# buffer.net
KiCad netlist of a schematic drawn in Altium Designer
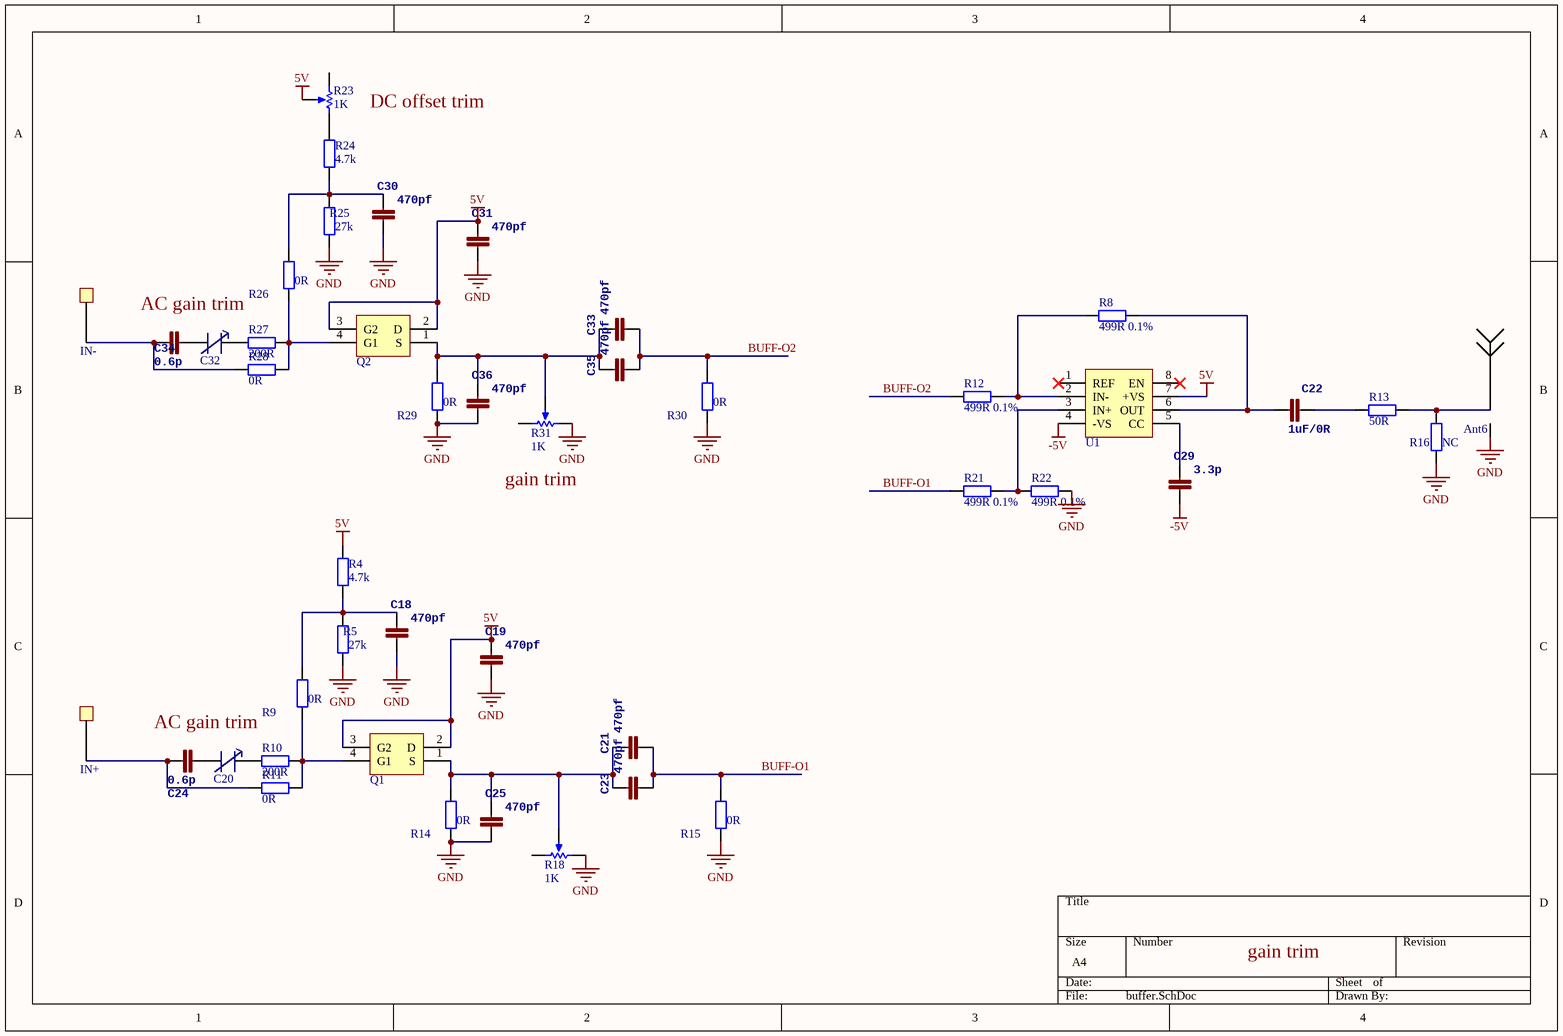
[diagram p0: buffer.SchDoc]

(export (version "E")
  (design (tool "Eeschema 10.0.6"))
  (components
    (comp (ref "Ant6") (value "Antenna") (footprint "SMA-HOLE") (libsource (lib "F4SDR") (part "Antenna")))
    (comp (ref "C18")
      (value "470pf")
      (footprint "0402")
      (description "<b>Capacitor</b>\nStandard 0603 ceramic capacitor, and 0.1\" leaded capacitor.")
      (fields (field (name "PARTNO") "CC0402ZRY5V7BB104"))
      (libsource (lib "") (part "CAP0402-CAP_1"))
    )
    (comp (ref "C19")
      (value "470pf")
      (footprint "0805")
      (description "<b>Capacitor</b>\nStandard 0603 ceramic capacitor, and 0.1\" leaded capacitor.")
      (fields (field (name "PARTNO") "CC0402ZRY5V7BB104"))
      (libsource (lib "") (part "CAP0402-CAP_1"))
    )
    (comp (ref "C20")
      (value "TZY2R200AC01R00")
      (footprint "TRIM_C")
      (libsource (lib "probe") (part "TRIM_C"))
    )
    (comp (ref "C21")
      (value "470pf")
      (footprint "0402")
      (description "<b>Capacitor</b>\nStandard 0603 ceramic capacitor, and 0.1\" leaded capacitor.")
      (fields (field (name "PARTNO") "CC0402ZRY5V7BB104"))
      (libsource (lib "pixhawk2") (part "CAP0402-CAP"))
    )
    (comp (ref "C22")
      (value "1uF/0R")
      (footprint "0402")
      (description "<b>Capacitor</b>\nStandard 0603 ceramic capacitor, and 0.1\" leaded capacitor.")
      (fields (field (name "PARTNO") "CC0402ZRY5V7BB104"))
      (libsource (lib "pixhawk2") (part "CAP0402-CAP"))
    )
    (comp (ref "C23")
      (value "470pf")
      (footprint "0402")
      (description "<b>Capacitor</b>\nStandard 0603 ceramic capacitor, and 0.1\" leaded capacitor.")
      (fields (field (name "PARTNO") "CC0402ZRY5V7BB104"))
      (libsource (lib "pixhawk2") (part "CAP0402-CAP"))
    )
    (comp (ref "C24")
      (value "0.6p")
      (footprint "0402")
      (description "<b>Capacitor</b>\nStandard 0603 ceramic capacitor, and 0.1\" leaded capacitor.")
      (fields (field (name "PARTNO") "CC0402ZRY5V7BB104"))
      (libsource (lib "pixhawk2") (part "CAP0402-CAP"))
    )
    (comp (ref "C25")
      (value "470pf")
      (footprint "0402")
      (description "<b>Capacitor</b>\nStandard 0603 ceramic capacitor, and 0.1\" leaded capacitor.")
      (fields (field (name "PARTNO") "CC0402ZRY5V7BB104"))
      (libsource (lib "") (part "CAP0402-CAP_1"))
    )
    (comp (ref "C29")
      (value "3.3p")
      (footprint "0402")
      (description "<b>Capacitor</b>\nStandard 0603 ceramic capacitor, and 0.1\" leaded capacitor.")
      (fields (field (name "PARTNO") "CC0402ZRY5V7BB104"))
      (libsource (lib "") (part "CAP0402-CAP_1"))
    )
    (comp (ref "C30")
      (value "470pf")
      (footprint "0402")
      (description "<b>Capacitor</b>\nStandard 0603 ceramic capacitor, and 0.1\" leaded capacitor.")
      (fields (field (name "PARTNO") "CC0402ZRY5V7BB104"))
      (libsource (lib "") (part "CAP0402-CAP_1"))
    )
    (comp (ref "C31")
      (value "470pf")
      (footprint "0805")
      (description "<b>Capacitor</b>\nStandard 0603 ceramic capacitor, and 0.1\" leaded capacitor.")
      (fields (field (name "PARTNO") "CC0402ZRY5V7BB104"))
      (libsource (lib "") (part "CAP0402-CAP_1"))
    )
    (comp (ref "C32")
      (value "TZY2R200AC01R00")
      (footprint "TRIM_C")
      (libsource (lib "probe") (part "TRIM_C"))
    )
    (comp (ref "C33")
      (value "470pf")
      (footprint "0402")
      (description "<b>Capacitor</b>\nStandard 0603 ceramic capacitor, and 0.1\" leaded capacitor.")
      (fields (field (name "PARTNO") "CC0402ZRY5V7BB104"))
      (libsource (lib "pixhawk2") (part "CAP0402-CAP"))
    )
    (comp (ref "C34")
      (value "0.6p")
      (footprint "0402")
      (description "<b>Capacitor</b>\nStandard 0603 ceramic capacitor, and 0.1\" leaded capacitor.")
      (fields (field (name "PARTNO") "CC0402ZRY5V7BB104"))
      (libsource (lib "pixhawk2") (part "CAP0402-CAP"))
    )
    (comp (ref "C35")
      (value "470pf")
      (footprint "0402")
      (description "<b>Capacitor</b>\nStandard 0603 ceramic capacitor, and 0.1\" leaded capacitor.")
      (fields (field (name "PARTNO") "CC0402ZRY5V7BB104"))
      (libsource (lib "pixhawk2") (part "CAP0402-CAP"))
    )
    (comp (ref "C36")
      (value "470pf")
      (footprint "0402")
      (description "<b>Capacitor</b>\nStandard 0603 ceramic capacitor, and 0.1\" leaded capacitor.")
      (fields (field (name "PARTNO") "CC0402ZRY5V7BB104"))
      (libsource (lib "") (part "CAP0402-CAP_1"))
    )
    (comp (ref "IN+") (value "TestPad") (footprint "TestPad") (libsource (lib "sch") (part "TestPad")))
    (comp (ref "IN-") (value "TestPad") (footprint "TestPad") (libsource (lib "sch") (part "TestPad")))
    (comp (ref "Q1") (value "BF998") (footprint "SOT143") (libsource (lib "probe") (part "BF998")))
    (comp (ref "Q2") (value "BF998") (footprint "SOT143") (libsource (lib "probe") (part "BF998")))
    (comp (ref "R4")
      (value "4.7k")
      (footprint "0402")
      (description "Resistor")
      (fields (field (name "PUBLISHER") "Altium Limited"))
      (libsource (lib "") (part "Res2_2"))
    )
    (comp (ref "R5")
      (value "27k")
      (footprint "0402")
      (description "Resistor")
      (fields (field (name "PUBLISHER") "Altium Limited"))
      (libsource (lib "") (part "Res2_1"))
    )
    (comp (ref "R8")
      (value "499R 0.1%")
      (footprint "0402")
      (description "Resistor")
      (fields (field (name "PUBLISHER") "Altium Limited"))
      (libsource (lib "Miscellaneous Devices") (part "Res2"))
    )
    (comp (ref "R9")
      (value "0R")
      (footprint "0402")
      (description "Resistor")
      (fields (field (name "PUBLISHER") "Altium Limited"))
      (libsource (lib "") (part "Res2_1"))
    )
    (comp (ref "R10")
      (value "200R")
      (footprint "0402")
      (description "Resistor")
      (fields (field (name "PUBLISHER") "Altium Limited"))
      (libsource (lib "Miscellaneous Devices") (part "Res2"))
    )
    (comp (ref "R11")
      (value "0R")
      (footprint "0402")
      (description "Resistor")
      (fields (field (name "PUBLISHER") "Altium Limited"))
      (libsource (lib "Miscellaneous Devices") (part "Res2"))
    )
    (comp (ref "R12")
      (value "499R 0.1%")
      (footprint "0402")
      (description "Resistor")
      (fields (field (name "PUBLISHER") "Altium Limited"))
      (libsource (lib "Miscellaneous Devices") (part "Res2"))
    )
    (comp (ref "R13")
      (value "50R")
      (footprint "0402")
      (description "Resistor")
      (fields (field (name "PUBLISHER") "Altium Limited"))
      (libsource (lib "Miscellaneous Devices") (part "Res2"))
    )
    (comp (ref "R14")
      (value "0R")
      (footprint "0402")
      (description "Resistor")
      (fields (field (name "PUBLISHER") "Altium Limited"))
      (libsource (lib "") (part "Res2_1"))
    )
    (comp (ref "R15")
      (value "0R")
      (footprint "0402")
      (description "Resistor")
      (fields (field (name "PUBLISHER") "Altium Limited"))
      (libsource (lib "") (part "Res2_1"))
    )
    (comp (ref "R16")
      (value "NC")
      (footprint "0402")
      (description "Resistor")
      (fields (field (name "PUBLISHER") "Altium Limited"))
      (libsource (lib "") (part "Res2_1"))
    )
    (comp (ref "R18")
      (value "1K")
      (footprint "POT1")
      (description "Potentiometer")
      (fields (field (name "Comment") "RPot") (field (name "PUBLISHER") "Altium Limited"))
      (libsource (lib "Miscellaneous Devices") (part "RPot"))
    )
    (comp (ref "R21")
      (value "499R 0.1%")
      (footprint "0402")
      (description "Resistor")
      (fields (field (name "PUBLISHER") "Altium Limited"))
      (libsource (lib "Miscellaneous Devices") (part "Res2"))
    )
    (comp (ref "R22")
      (value "499R 0.1%")
      (footprint "0402")
      (description "Resistor")
      (fields (field (name "PUBLISHER") "Altium Limited"))
      (libsource (lib "") (part "Res2_3"))
    )
    (comp (ref "R23")
      (value "1K")
      (footprint "POT1")
      (description "Potentiometer")
      (fields (field (name "Comment") "RPot") (field (name "PUBLISHER") "Altium Limited"))
      (libsource (lib "Miscellaneous Devices") (part "RPot"))
    )
    (comp (ref "R24")
      (value "4.7k")
      (footprint "0402")
      (description "Resistor")
      (fields (field (name "PUBLISHER") "Altium Limited"))
      (libsource (lib "") (part "Res2_2"))
    )
    (comp (ref "R25")
      (value "27k")
      (footprint "0402")
      (description "Resistor")
      (fields (field (name "PUBLISHER") "Altium Limited"))
      (libsource (lib "") (part "Res2_1"))
    )
    (comp (ref "R26")
      (value "0R")
      (footprint "0402")
      (description "Resistor")
      (fields (field (name "PUBLISHER") "Altium Limited"))
      (libsource (lib "") (part "Res2_1"))
    )
    (comp (ref "R27")
      (value "200R")
      (footprint "0402")
      (description "Resistor")
      (fields (field (name "PUBLISHER") "Altium Limited"))
      (libsource (lib "Miscellaneous Devices") (part "Res2"))
    )
    (comp (ref "R28")
      (value "0R")
      (footprint "0402")
      (description "Resistor")
      (fields (field (name "PUBLISHER") "Altium Limited"))
      (libsource (lib "Miscellaneous Devices") (part "Res2"))
    )
    (comp (ref "R29")
      (value "0R")
      (footprint "0402")
      (description "Resistor")
      (fields (field (name "PUBLISHER") "Altium Limited"))
      (libsource (lib "") (part "Res2_1"))
    )
    (comp (ref "R30")
      (value "0R")
      (footprint "0402")
      (description "Resistor")
      (fields (field (name "PUBLISHER") "Altium Limited"))
      (libsource (lib "") (part "Res2_1"))
    )
    (comp (ref "R31")
      (value "1K")
      (footprint "POT1")
      (description "Potentiometer")
      (fields (field (name "Comment") "RPot") (field (name "PUBLISHER") "Altium Limited"))
      (libsource (lib "Miscellaneous Devices") (part "RPot"))
    )
    (comp (ref "U1") (value "AD8021") (footprint "SO8") (libsource (lib "probe") (part "AD8021")))
  )
  (nets
    (net (code "1") (name "-5V") (class "Default")
      (node (ref "C29") (pin "1") (pinfunction "1_1") (pintype "passive"))
      (node (ref "U1") (pin "4") (pinfunction "-VS_4") (pintype "passive"))
    )
    (net (code "2") (name "/BUFF-O1") (class "Default")
      (node (ref "C21") (pin "1") (pinfunction "1_1") (pintype "passive"))
      (node (ref "C23") (pin "1") (pinfunction "1_1") (pintype "passive"))
      (node (ref "R15") (pin "1") (pinfunction "1_1") (pintype "passive"))
      (node (ref "R21") (pin "1") (pinfunction "1_1") (pintype "passive"))
    )
    (net (code "3") (name "/BUFF-O2") (class "Default")
      (node (ref "C33") (pin "1") (pinfunction "1_1") (pintype "passive"))
      (node (ref "C35") (pin "1") (pinfunction "1_1") (pintype "passive"))
      (node (ref "R12") (pin "1") (pinfunction "1_1") (pintype "passive"))
      (node (ref "R30") (pin "1") (pinfunction "1_1") (pintype "passive"))
    )
    (net (code "4") (name "5V") (class "Default")
      (node (ref "C19") (pin "2") (pinfunction "2_2") (pintype "passive"))
      (node (ref "C31") (pin "2") (pinfunction "2_2") (pintype "passive"))
      (node (ref "Q1") (pin "2") (pinfunction "D_2") (pintype "passive"))
      (node (ref "Q1") (pin "3") (pinfunction "G2_3") (pintype "passive"))
      (node (ref "Q2") (pin "2") (pinfunction "D_2") (pintype "passive"))
      (node (ref "Q2") (pin "3") (pinfunction "G2_3") (pintype "passive"))
      (node (ref "R23") (pin "3") (pinfunction "TAP_3") (pintype "passive"))
      (node (ref "R4") (pin "2") (pinfunction "2_2") (pintype "passive"))
      (node (ref "U1") (pin "7") (pinfunction "+VS_7") (pintype "passive"))
    )
    (net (code "5") (name "GND") (class "Default")
      (node (ref "Ant6") (pin "GND") (pinfunction "G_GND") (pintype "passive"))
      (node (ref "C18") (pin "1") (pinfunction "1_1") (pintype "passive"))
      (node (ref "C19") (pin "1") (pinfunction "1_1") (pintype "passive"))
      (node (ref "C25") (pin "1") (pinfunction "1_1") (pintype "passive"))
      (node (ref "C30") (pin "1") (pinfunction "1_1") (pintype "passive"))
      (node (ref "C31") (pin "1") (pinfunction "1_1") (pintype "passive"))
      (node (ref "C36") (pin "1") (pinfunction "1_1") (pintype "passive"))
      (node (ref "R14") (pin "2") (pinfunction "2_2") (pintype "passive"))
      (node (ref "R15") (pin "2") (pinfunction "2_2") (pintype "passive"))
      (node (ref "R16") (pin "2") (pinfunction "2_2") (pintype "passive"))
      (node (ref "R18") (pin "1") (pinfunction "TOP_1") (pintype "passive"))
      (node (ref "R22") (pin "1") (pinfunction "1_1") (pintype "passive"))
      (node (ref "R25") (pin "2") (pinfunction "2_2") (pintype "passive"))
      (node (ref "R29") (pin "2") (pinfunction "2_2") (pintype "passive"))
      (node (ref "R30") (pin "2") (pinfunction "2_2") (pintype "passive"))
      (node (ref "R31") (pin "1") (pinfunction "TOP_1") (pintype "passive"))
      (node (ref "R5") (pin "2") (pinfunction "2_2") (pintype "passive"))
    )
    (net (code "6") (name "Net-(Ant6-Pad1)") (class "Default")
      (node (ref "Ant6") (pin "1") (pinfunction "1_1") (pintype "passive"))
      (node (ref "R13") (pin "2") (pinfunction "2_2") (pintype "passive"))
      (node (ref "R16") (pin "1") (pinfunction "1_1") (pintype "passive"))
    )
    (net (code "7") (name "Net-(C18-Pad2)") (class "Default")
      (node (ref "C18") (pin "2") (pinfunction "2_2") (pintype "passive"))
      (node (ref "R4") (pin "1") (pinfunction "1_1") (pintype "passive"))
      (node (ref "R5") (pin "1") (pinfunction "1_1") (pintype "passive"))
      (node (ref "R9") (pin "1") (pinfunction "1_1") (pintype "passive"))
    )
    (net (code "8") (name "Net-(C20-Pad1)") (class "Default")
      (node (ref "C20") (pin "1") (pinfunction "1_1") (pintype "passive"))
      (node (ref "C24") (pin "1") (pinfunction "1_1") (pintype "passive"))
    )
    (net (code "9") (name "Net-(C20-Pad2)") (class "Default")
      (node (ref "C20") (pin "2") (pinfunction "2_2") (pintype "passive"))
      (node (ref "R10") (pin "1") (pinfunction "1_1") (pintype "passive"))
    )
    (net (code "10") (name "Net-(C22-Pad1)") (class "Default")
      (node (ref "C22") (pin "1") (pinfunction "1_1") (pintype "passive"))
      (node (ref "R13") (pin "1") (pinfunction "1_1") (pintype "passive"))
    )
    (net (code "11") (name "Net-(C30-Pad2)") (class "Default")
      (node (ref "C30") (pin "2") (pinfunction "2_2") (pintype "passive"))
      (node (ref "R24") (pin "1") (pinfunction "1_1") (pintype "passive"))
      (node (ref "R25") (pin "1") (pinfunction "1_1") (pintype "passive"))
      (node (ref "R26") (pin "1") (pinfunction "1_1") (pintype "passive"))
    )
    (net (code "12") (name "Net-(C32-Pad1)") (class "Default")
      (node (ref "C32") (pin "1") (pinfunction "1_1") (pintype "passive"))
      (node (ref "C34") (pin "1") (pinfunction "1_1") (pintype "passive"))
    )
    (net (code "13") (name "Net-(C32-Pad2)") (class "Default")
      (node (ref "C32") (pin "2") (pinfunction "2_2") (pintype "passive"))
      (node (ref "R27") (pin "1") (pinfunction "1_1") (pintype "passive"))
    )
    (net (code "14") (name "Net-(IN+-3)") (class "Default")
      (node (ref "C24") (pin "2") (pinfunction "2_2") (pintype "passive"))
      (node (ref "IN+") (pin "1") (pinfunction "3_1") (pintype "passive"))
      (node (ref "R11") (pin "1") (pinfunction "1_1") (pintype "passive"))
    )
    (net (code "15") (name "Net-(IN--3)") (class "Default")
      (node (ref "C34") (pin "2") (pinfunction "2_2") (pintype "passive"))
      (node (ref "IN-") (pin "1") (pinfunction "3_1") (pintype "passive"))
      (node (ref "R28") (pin "1") (pinfunction "1_1") (pintype "passive"))
    )
    (net (code "16") (name "Net-(Q1-G1)") (class "Default")
      (node (ref "Q1") (pin "4") (pinfunction "G1_4") (pintype "passive"))
      (node (ref "R10") (pin "2") (pinfunction "2_2") (pintype "passive"))
      (node (ref "R11") (pin "2") (pinfunction "2_2") (pintype "passive"))
      (node (ref "R9") (pin "2") (pinfunction "2_2") (pintype "passive"))
    )
    (net (code "17") (name "Net-(Q1-S)") (class "Default")
      (node (ref "C21") (pin "2") (pinfunction "2_2") (pintype "passive"))
      (node (ref "C23") (pin "2") (pinfunction "2_2") (pintype "passive"))
      (node (ref "C25") (pin "2") (pinfunction "2_2") (pintype "passive"))
      (node (ref "Q1") (pin "1") (pinfunction "S_1") (pintype "passive"))
      (node (ref "R14") (pin "1") (pinfunction "1_1") (pintype "passive"))
      (node (ref "R18") (pin "3") (pinfunction "TAP_3") (pintype "passive"))
    )
    (net (code "18") (name "Net-(Q2-G1)") (class "Default")
      (node (ref "Q2") (pin "4") (pinfunction "G1_4") (pintype "passive"))
      (node (ref "R26") (pin "2") (pinfunction "2_2") (pintype "passive"))
      (node (ref "R27") (pin "2") (pinfunction "2_2") (pintype "passive"))
      (node (ref "R28") (pin "2") (pinfunction "2_2") (pintype "passive"))
    )
    (net (code "19") (name "Net-(Q2-S)") (class "Default")
      (node (ref "C33") (pin "2") (pinfunction "2_2") (pintype "passive"))
      (node (ref "C35") (pin "2") (pinfunction "2_2") (pintype "passive"))
      (node (ref "C36") (pin "2") (pinfunction "2_2") (pintype "passive"))
      (node (ref "Q2") (pin "1") (pinfunction "S_1") (pintype "passive"))
      (node (ref "R29") (pin "1") (pinfunction "1_1") (pintype "passive"))
      (node (ref "R31") (pin "3") (pinfunction "TAP_3") (pintype "passive"))
    )
    (net (code "20") (name "Net-(R23-BOT)") (class "Default")
      (node (ref "R23") (pin "2") (pinfunction "BOT_2") (pintype "passive"))
      (node (ref "R24") (pin "2") (pinfunction "2_2") (pintype "passive"))
    )
    (net (code "21") (name "Net-(U1-CC)") (class "Default")
      (node (ref "C29") (pin "2") (pinfunction "2_2") (pintype "passive"))
      (node (ref "U1") (pin "5") (pinfunction "CC_5") (pintype "passive"))
    )
    (net (code "22") (name "Net-(U1-IN+)") (class "Default")
      (node (ref "R21") (pin "2") (pinfunction "2_2") (pintype "passive"))
      (node (ref "R22") (pin "2") (pinfunction "2_2") (pintype "passive"))
      (node (ref "U1") (pin "3") (pinfunction "IN+_3") (pintype "passive"))
    )
    (net (code "23") (name "Net-(U1-IN-)") (class "Default")
      (node (ref "R12") (pin "2") (pinfunction "2_2") (pintype "passive"))
      (node (ref "R8") (pin "1") (pinfunction "1_1") (pintype "passive"))
      (node (ref "U1") (pin "2") (pinfunction "IN-_2") (pintype "passive"))
    )
    (net (code "24") (name "Net-(U1-OUT)") (class "Default")
      (node (ref "C22") (pin "2") (pinfunction "2_2") (pintype "passive"))
      (node (ref "R8") (pin "2") (pinfunction "2_2") (pintype "passive"))
      (node (ref "U1") (pin "6") (pinfunction "OUT_6") (pintype "passive"))
    )
    (net (code "25") (name "unconnected-(R18-BOT-Pad2)") (class "Default")
      (node (ref "R18") (pin "2") (pinfunction "BOT_2") (pintype "passive"))
    )
    (net (code "26") (name "unconnected-(R23-TOP-Pad1)") (class "Default")
      (node (ref "R23") (pin "1") (pinfunction "TOP_1") (pintype "passive"))
    )
    (net (code "27") (name "unconnected-(R31-BOT-Pad2)") (class "Default")
      (node (ref "R31") (pin "2") (pinfunction "BOT_2") (pintype "passive"))
    )
    (net (code "28") (name "unconnected-(U1-EN-Pad8)") (class "Default")
      (node (ref "U1") (pin "8") (pinfunction "EN_8") (pintype "passive+no_connect"))
    )
    (net (code "29") (name "unconnected-(U1-REF-Pad1)") (class "Default")
      (node (ref "U1") (pin "1") (pinfunction "REF_1") (pintype "passive+no_connect"))
    )
  )
)
